# sheet1.net
KiCad netlist of a schematic drawn in Altium Designer
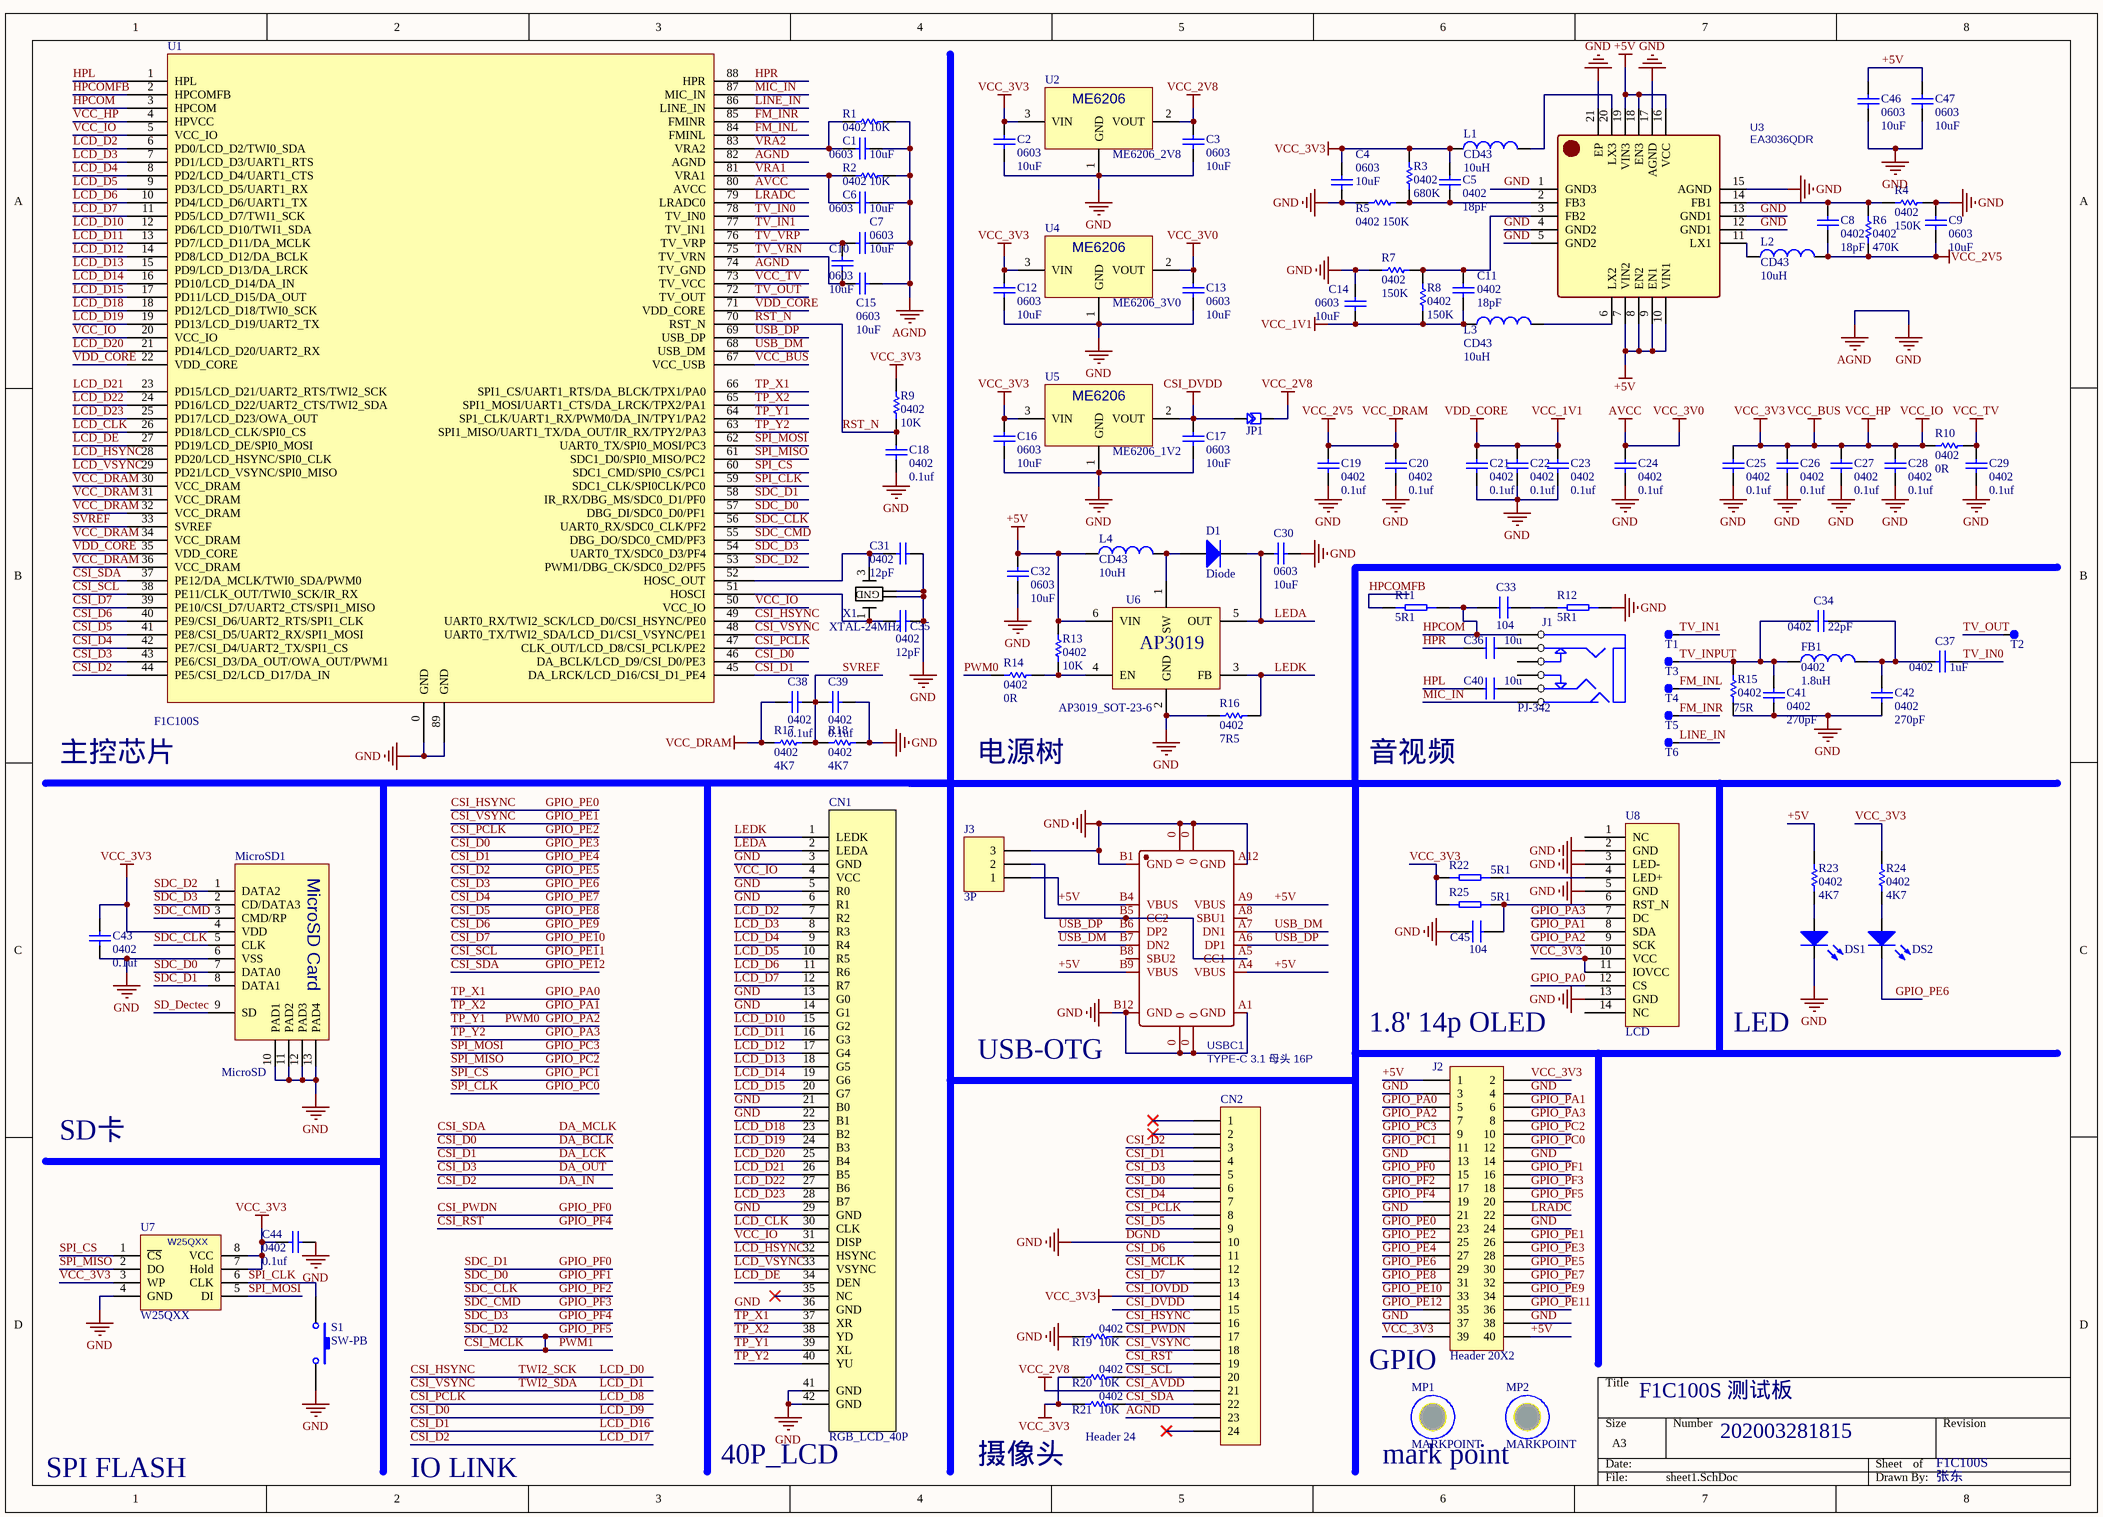
[diagram p0: sheet1.SchDoc]

(export (version "E")
  (design (tool "Eeschema 10.0.6"))
  (components
    (comp (ref "C1")
      (value "0603")
      (footprint "0603AC")
      (description "Capacitor")
      (fields (field (name "ALTIUM_VALUE") "10uF") (field (name "PUBLISHER") "Altium Limited"))
      (libsource (lib "Miscellaneous Devices") (part "Cap"))
    )
    (comp (ref "C2")
      (value "0603")
      (footprint "0603AC")
      (description "Capacitor")
      (fields (field (name "ALTIUM_VALUE") "10uF") (field (name "PUBLISHER") "Altium Limited"))
      (libsource (lib "Miscellaneous Devices") (part "Cap"))
    )
    (comp (ref "C3")
      (value "0603")
      (footprint "0603AC")
      (description "Capacitor")
      (fields (field (name "ALTIUM_VALUE") "10uF") (field (name "PUBLISHER") "Altium Limited"))
      (libsource (lib "Miscellaneous Devices") (part "Cap"))
    )
    (comp (ref "C4")
      (value "0603")
      (footprint "0603AC")
      (description "Capacitor")
      (fields (field (name "ALTIUM_VALUE") "10uF") (field (name "PUBLISHER") "Altium Limited"))
      (libsource (lib "Miscellaneous Devices") (part "Cap"))
    )
    (comp (ref "C5")
      (value "0402")
      (footprint "0402AC")
      (description "Capacitor")
      (fields (field (name "ALTIUM_VALUE") "18pF") (field (name "PUBLISHER") "Altium Limited"))
      (libsource (lib "Miscellaneous Devices") (part "Cap"))
    )
    (comp (ref "C6")
      (value "0603")
      (footprint "0603AC")
      (description "Capacitor")
      (fields (field (name "ALTIUM_VALUE") "10uF") (field (name "PUBLISHER") "Altium Limited"))
      (libsource (lib "Miscellaneous Devices") (part "Cap"))
    )
    (comp (ref "C7")
      (value "0603")
      (footprint "0603AC")
      (description "Capacitor")
      (fields (field (name "ALTIUM_VALUE") "10uF") (field (name "PUBLISHER") "Altium Limited"))
      (libsource (lib "Miscellaneous Devices") (part "Cap"))
    )
    (comp (ref "C8")
      (value "0402")
      (footprint "0402AC")
      (description "Capacitor")
      (fields (field (name "ALTIUM_VALUE") "18pF") (field (name "PUBLISHER") "Altium Limited"))
      (libsource (lib "Miscellaneous Devices") (part "Cap"))
    )
    (comp (ref "C9")
      (value "0603")
      (footprint "0603AC")
      (description "Capacitor")
      (fields (field (name "ALTIUM_VALUE") "10uF") (field (name "PUBLISHER") "Altium Limited"))
      (libsource (lib "Miscellaneous Devices") (part "Cap"))
    )
    (comp (ref "C10")
      (value "0603")
      (footprint "0603AC")
      (description "Capacitor")
      (fields (field (name "ALTIUM_VALUE") "10uF") (field (name "PUBLISHER") "Altium Limited"))
      (libsource (lib "Miscellaneous Devices") (part "Cap"))
    )
    (comp (ref "C11")
      (value "0402")
      (footprint "0402AC")
      (description "Capacitor")
      (fields (field (name "ALTIUM_VALUE") "18pF") (field (name "PUBLISHER") "Altium Limited"))
      (libsource (lib "Miscellaneous Devices") (part "Cap"))
    )
    (comp (ref "C12")
      (value "0603")
      (footprint "0603AC")
      (description "Capacitor")
      (fields (field (name "ALTIUM_VALUE") "10uF") (field (name "PUBLISHER") "Altium Limited"))
      (libsource (lib "Miscellaneous Devices") (part "Cap"))
    )
    (comp (ref "C13")
      (value "0603")
      (footprint "0603AC")
      (description "Capacitor")
      (fields (field (name "ALTIUM_VALUE") "10uF") (field (name "PUBLISHER") "Altium Limited"))
      (libsource (lib "Miscellaneous Devices") (part "Cap"))
    )
    (comp (ref "C14")
      (value "0603")
      (footprint "0603AC")
      (description "Capacitor")
      (fields (field (name "ALTIUM_VALUE") "10uF") (field (name "PUBLISHER") "Altium Limited"))
      (libsource (lib "Miscellaneous Devices") (part "Cap"))
    )
    (comp (ref "C15")
      (value "0603")
      (footprint "0603AC")
      (description "Capacitor")
      (fields (field (name "ALTIUM_VALUE") "10uF") (field (name "PUBLISHER") "Altium Limited"))
      (libsource (lib "Miscellaneous Devices") (part "Cap"))
    )
    (comp (ref "C16")
      (value "0603")
      (footprint "0603AC")
      (description "Capacitor")
      (fields (field (name "ALTIUM_VALUE") "10uF") (field (name "PUBLISHER") "Altium Limited"))
      (libsource (lib "Miscellaneous Devices") (part "Cap"))
    )
    (comp (ref "C17")
      (value "0603")
      (footprint "0603AC")
      (description "Capacitor")
      (fields (field (name "ALTIUM_VALUE") "10uF") (field (name "PUBLISHER") "Altium Limited"))
      (libsource (lib "Miscellaneous Devices") (part "Cap"))
    )
    (comp (ref "C18")
      (value "0402")
      (footprint "0402AC")
      (description "Capacitor")
      (fields (field (name "ALTIUM_VALUE") "0.1uf") (field (name "PUBLISHER") "Altium Limited"))
      (libsource (lib "Miscellaneous Devices") (part "Cap"))
    )
    (comp (ref "C19")
      (value "0402")
      (footprint "0402AC")
      (description "Capacitor")
      (fields (field (name "ALTIUM_VALUE") "0.1uf") (field (name "PUBLISHER") "Altium Limited"))
      (libsource (lib "Miscellaneous Devices") (part "Cap"))
    )
    (comp (ref "C20")
      (value "0402")
      (footprint "0402AC")
      (description "Capacitor")
      (fields (field (name "ALTIUM_VALUE") "0.1uf") (field (name "PUBLISHER") "Altium Limited"))
      (libsource (lib "Miscellaneous Devices") (part "Cap"))
    )
    (comp (ref "C21")
      (value "0402")
      (footprint "0402AC")
      (description "Capacitor")
      (fields (field (name "ALTIUM_VALUE") "0.1uf") (field (name "PUBLISHER") "Altium Limited"))
      (libsource (lib "Miscellaneous Devices") (part "Cap"))
    )
    (comp (ref "C22")
      (value "0402")
      (footprint "0402AC")
      (description "Capacitor")
      (fields (field (name "ALTIUM_VALUE") "0.1uf") (field (name "PUBLISHER") "Altium Limited"))
      (libsource (lib "Miscellaneous Devices") (part "Cap"))
    )
    (comp (ref "C23")
      (value "0402")
      (footprint "0402AC")
      (description "Capacitor")
      (fields (field (name "ALTIUM_VALUE") "0.1uf") (field (name "PUBLISHER") "Altium Limited"))
      (libsource (lib "Miscellaneous Devices") (part "Cap"))
    )
    (comp (ref "C24")
      (value "0402")
      (footprint "0402AC")
      (description "Capacitor")
      (fields (field (name "ALTIUM_VALUE") "0.1uf") (field (name "PUBLISHER") "Altium Limited"))
      (libsource (lib "Miscellaneous Devices") (part "Cap"))
    )
    (comp (ref "C25")
      (value "0402")
      (footprint "0402AC")
      (description "Capacitor")
      (fields (field (name "ALTIUM_VALUE") "0.1uf") (field (name "PUBLISHER") "Altium Limited"))
      (libsource (lib "Miscellaneous Devices") (part "Cap"))
    )
    (comp (ref "C26")
      (value "0402")
      (footprint "0402AC")
      (description "Capacitor")
      (fields (field (name "ALTIUM_VALUE") "0.1uf") (field (name "PUBLISHER") "Altium Limited"))
      (libsource (lib "Miscellaneous Devices") (part "Cap"))
    )
    (comp (ref "C27")
      (value "0402")
      (footprint "0402AC")
      (description "Capacitor")
      (fields (field (name "ALTIUM_VALUE") "0.1uf") (field (name "PUBLISHER") "Altium Limited"))
      (libsource (lib "Miscellaneous Devices") (part "Cap"))
    )
    (comp (ref "C28")
      (value "0402")
      (footprint "0402AC")
      (description "Capacitor")
      (fields (field (name "ALTIUM_VALUE") "0.1uf") (field (name "PUBLISHER") "Altium Limited"))
      (libsource (lib "Miscellaneous Devices") (part "Cap"))
    )
    (comp (ref "C29")
      (value "0402")
      (footprint "0402AC")
      (description "Capacitor")
      (fields (field (name "ALTIUM_VALUE") "0.1uf") (field (name "PUBLISHER") "Altium Limited"))
      (libsource (lib "Miscellaneous Devices") (part "Cap"))
    )
    (comp (ref "C30")
      (value "0603")
      (footprint "0603AC")
      (description "Capacitor")
      (fields (field (name "ALTIUM_VALUE") "10uF") (field (name "PUBLISHER") "Altium Limited"))
      (libsource (lib "Miscellaneous Devices") (part "Cap"))
    )
    (comp (ref "C31")
      (value "0402")
      (footprint "0402AC")
      (description "Capacitor")
      (fields (field (name "ALTIUM_VALUE") "12pF") (field (name "PUBLISHER") "Altium Limited"))
      (libsource (lib "Miscellaneous Devices") (part "Cap"))
    )
    (comp (ref "C32")
      (value "0603")
      (footprint "0603AC")
      (description "Capacitor")
      (fields (field (name "ALTIUM_VALUE") "10uF") (field (name "PUBLISHER") "Altium Limited"))
      (libsource (lib "Miscellaneous Devices") (part "Cap"))
    )
    (comp (ref "C33")
      (value "104")
      (footprint "0402C")
      (description "SMD-CAP")
      (libsource (lib "lpi-nano-dock") (part "CAP"))
    )
    (comp (ref "C34")
      (value "0402")
      (footprint "0402AC")
      (description "Capacitor")
      (fields (field (name "ALTIUM_VALUE") "22pF") (field (name "PUBLISHER") "Altium Limited"))
      (libsource (lib "Miscellaneous Devices") (part "Cap"))
    )
    (comp (ref "C35")
      (value "0402")
      (footprint "0402AC")
      (description "Capacitor")
      (fields (field (name "ALTIUM_VALUE") "12pF") (field (name "PUBLISHER") "Altium Limited"))
      (libsource (lib "Miscellaneous Devices") (part "Cap"))
    )
    (comp (ref "C36")
      (value "10u")
      (footprint "0402C")
      (description "SMD-CAP")
      (libsource (lib "lpi-nano-dock") (part "CAP"))
    )
    (comp (ref "C37")
      (value "0402")
      (footprint "0402AC")
      (description "Capacitor")
      (fields (field (name "ALTIUM_VALUE") "1uF") (field (name "PUBLISHER") "Altium Limited"))
      (libsource (lib "Miscellaneous Devices") (part "Cap"))
    )
    (comp (ref "C38")
      (value "0402")
      (footprint "0402AC")
      (description "Capacitor")
      (fields (field (name "ALTIUM_VALUE") "0.1uf") (field (name "PUBLISHER") "Altium Limited"))
      (libsource (lib "Miscellaneous Devices") (part "Cap"))
    )
    (comp (ref "C39")
      (value "0402")
      (footprint "0402AC")
      (description "Capacitor")
      (fields (field (name "ALTIUM_VALUE") "0.1uf") (field (name "PUBLISHER") "Altium Limited"))
      (libsource (lib "Miscellaneous Devices") (part "Cap"))
    )
    (comp (ref "C40")
      (value "10u")
      (footprint "0402C")
      (description "SMD-CAP")
      (libsource (lib "lpi-nano-dock") (part "CAP"))
    )
    (comp (ref "C41")
      (value "0402")
      (footprint "0402AC")
      (description "Capacitor")
      (fields (field (name "ALTIUM_VALUE") "270pF") (field (name "PUBLISHER") "Altium Limited"))
      (libsource (lib "Miscellaneous Devices") (part "Cap"))
    )
    (comp (ref "C42")
      (value "0402")
      (footprint "0402AC")
      (description "Capacitor")
      (fields (field (name "ALTIUM_VALUE") "270pF") (field (name "PUBLISHER") "Altium Limited"))
      (libsource (lib "Miscellaneous Devices") (part "Cap"))
    )
    (comp (ref "C43")
      (value "0402")
      (footprint "0402AC")
      (description "Capacitor")
      (fields (field (name "ALTIUM_VALUE") "0.1uf") (field (name "PUBLISHER") "Altium Limited"))
      (libsource (lib "Miscellaneous Devices") (part "Cap"))
    )
    (comp (ref "C44")
      (value "0402")
      (footprint "0402AC")
      (description "Capacitor")
      (fields (field (name "ALTIUM_VALUE") "0.1uf") (field (name "PUBLISHER") "Altium Limited"))
      (libsource (lib "Miscellaneous Devices") (part "Cap"))
    )
    (comp (ref "C45")
      (value "104")
      (footprint "0402C")
      (description "SMD-CAP")
      (libsource (lib "lpi-nano-dock") (part "CAP"))
    )
    (comp (ref "C46")
      (value "0603")
      (footprint "0603AC")
      (description "Capacitor")
      (fields (field (name "ALTIUM_VALUE") "10uF") (field (name "PUBLISHER") "Altium Limited"))
      (libsource (lib "Miscellaneous Devices") (part "Cap"))
    )
    (comp (ref "C47")
      (value "0603")
      (footprint "0603AC")
      (description "Capacitor")
      (fields (field (name "ALTIUM_VALUE") "10uF") (field (name "PUBLISHER") "Altium Limited"))
      (libsource (lib "Miscellaneous Devices") (part "Cap"))
    )
    (comp (ref "CN1")
      (value "RGB_LCD_40P")
      (footprint "FH19C-40S-0.5SH")
      (libsource (lib "7426SCH") (part "RGB_LCD_40P"))
    )
    (comp (ref "CN2")
      (value "Header 24")
      (footprint "FH19C-24S-0.5SH")
      (description "Header, 24-Pin")
      (fields (field (name "PUBLISHER") "Altium Limited"))
      (libsource (lib "Miscellaneous Connectors") (part "Header 24"))
    )
    (comp (ref "D1")
      (value "Diode")
      (footprint "SOD123")
      (description "Default Diode")
      (fields (field (name "PUBLISHER") "Altium Limited"))
      (libsource (lib "Miscellaneous Devices") (part "Diode"))
    )
    (comp (ref "DS1") (value "LED") (footprint "LED 0805B") (libsource (lib "QT") (part "LED")))
    (comp (ref "DS2") (value "LED") (footprint "LED 0805B") (libsource (lib "QT") (part "LED")))
    (comp (ref "FB1")
      (value "0402")
      (footprint "0402AR")
      (description "CD43")
      (fields (field (name "ALTIUM_VALUE") "1.8uH") (field (name "PUBLISHER") "Altium Limited"))
      (libsource (lib "Miscellaneous Devices") (part "Inductor"))
    )
    (comp (ref "J1") (value "PJ-342") (footprint "PJ-342") (libsource (lib "lpi-nano-dock") (part "PJ-342")))
    (comp (ref "J2")
      (value "Header 20X2")
      (footprint "HDR2X20")
      (description "Header, 20-Pin, Dual row")
      (fields (field (name "PUBLISHER") "Altium Limited"))
      (libsource (lib "Miscellaneous Connectors") (part "Header 20X2"))
    )
    (comp (ref "J3") (value "3P") (footprint "3P") (libsource (lib "常用元件库") (part "3P")))
    (comp (ref "JP1") (value "SW-PAD-2") (footprint "SW-PAD-2") (libsource (lib "7426SCH") (part "SW-PAD-2")))
    (comp (ref "L1")
      (value "CD43")
      (footprint "2520")
      (fields (field (name "ALTIUM_VALUE") "10uH") (field (name "PUBLISHER") "Altium Limited"))
      (libsource (lib "Miscellaneous Devices") (part "Inductor"))
    )
    (comp (ref "L2")
      (value "CD43")
      (footprint "2520")
      (fields (field (name "ALTIUM_VALUE") "10uH") (field (name "PUBLISHER") "Altium Limited"))
      (libsource (lib "Miscellaneous Devices") (part "Inductor"))
    )
    (comp (ref "L3")
      (value "CD43")
      (footprint "2520")
      (fields (field (name "ALTIUM_VALUE") "10uH") (field (name "PUBLISHER") "Altium Limited"))
      (libsource (lib "Miscellaneous Devices") (part "Inductor"))
    )
    (comp (ref "L4")
      (value "CD43")
      (footprint "2520")
      (fields (field (name "ALTIUM_VALUE") "10uH") (field (name "PUBLISHER") "Altium Limited"))
      (libsource (lib "Miscellaneous Devices") (part "Inductor"))
    )
    (comp (ref "MicroSD1")
      (value "MicroSD")
      (footprint "MicroSD")
      (libsource (lib "7426SCH") (part "MicroSD"))
    )
    (comp (ref "MP1")
      (value "MARKPOINT")
      (footprint "MARKPOINT")
      (libsource (lib "7426SCH") (part "MARKPOINT"))
    )
    (comp (ref "MP2")
      (value "MARKPOINT")
      (footprint "MARKPOINT")
      (libsource (lib "7426SCH") (part "MARKPOINT"))
    )
    (comp (ref "R1")
      (value "0402")
      (footprint "0402AR")
      (description "Resistor")
      (fields (field (name "ALTIUM_VALUE") "10K") (field (name "PUBLISHER") "Altium Limited"))
      (libsource (lib "Miscellaneous Devices") (part "Res1"))
    )
    (comp (ref "R2")
      (value "0402")
      (footprint "0402AR")
      (description "Resistor")
      (fields (field (name "ALTIUM_VALUE") "10K") (field (name "PUBLISHER") "Altium Limited"))
      (libsource (lib "Miscellaneous Devices") (part "Res1"))
    )
    (comp (ref "R3")
      (value "0402")
      (footprint "0402AR")
      (fields (field (name "ALTIUM_VALUE") "680K") (field (name "PUBLISHER") "Altium Limited"))
      (libsource (lib "Miscellaneous Devices") (part "Res1"))
    )
    (comp (ref "R4")
      (value "0402")
      (footprint "0402AR")
      (description "Resistor")
      (fields (field (name "ALTIUM_VALUE") "150K") (field (name "PUBLISHER") "Altium Limited"))
      (libsource (lib "Miscellaneous Devices") (part "Res1"))
    )
    (comp (ref "R5")
      (value "0402")
      (footprint "0402AR")
      (description "Resistor")
      (fields (field (name "ALTIUM_VALUE") "150K") (field (name "PUBLISHER") "Altium Limited"))
      (libsource (lib "Miscellaneous Devices") (part "Res1"))
    )
    (comp (ref "R6")
      (value "0402")
      (footprint "0402AR")
      (fields (field (name "ALTIUM_VALUE") "470K") (field (name "PUBLISHER") "Altium Limited"))
      (libsource (lib "Miscellaneous Devices") (part "Res1"))
    )
    (comp (ref "R7")
      (value "0402")
      (footprint "0402AR")
      (fields (field (name "ALTIUM_VALUE") "150K") (field (name "PUBLISHER") "Altium Limited"))
      (libsource (lib "Miscellaneous Devices") (part "Res1"))
    )
    (comp (ref "R8")
      (value "0402")
      (footprint "0402AR")
      (fields (field (name "ALTIUM_VALUE") "150K") (field (name "PUBLISHER") "Altium Limited"))
      (libsource (lib "Miscellaneous Devices") (part "Res1"))
    )
    (comp (ref "R9")
      (value "0402")
      (footprint "0402AR")
      (fields (field (name "ALTIUM_VALUE") "10K") (field (name "PUBLISHER") "Altium Limited"))
      (libsource (lib "Miscellaneous Devices") (part "Res1"))
    )
    (comp (ref "R10")
      (value "0402")
      (footprint "0402AR")
      (fields (field (name "ALTIUM_VALUE") "0R") (field (name "PUBLISHER") "Altium Limited"))
      (libsource (lib "Miscellaneous Devices") (part "Res1"))
    )
    (comp (ref "R11") (value "5R1") (footprint "0402R") (libsource (lib "lpi-nano-dock") (part "R")))
    (comp (ref "R12") (value "5R1") (footprint "0402R") (libsource (lib "lpi-nano-dock") (part "R")))
    (comp (ref "R13")
      (value "0402")
      (footprint "0402AR")
      (fields (field (name "ALTIUM_VALUE") "10K") (field (name "PUBLISHER") "Altium Limited"))
      (libsource (lib "Miscellaneous Devices") (part "Res1"))
    )
    (comp (ref "R14")
      (value "0402")
      (footprint "0402AR")
      (fields (field (name "ALTIUM_VALUE") "0R") (field (name "PUBLISHER") "Altium Limited"))
      (libsource (lib "Miscellaneous Devices") (part "Res1"))
    )
    (comp (ref "R15")
      (value "0402")
      (footprint "0402AR")
      (description "Resistor")
      (fields (field (name "ALTIUM_VALUE") "75R") (field (name "PUBLISHER") "Altium Limited"))
      (libsource (lib "Miscellaneous Devices") (part "Res1"))
    )
    (comp (ref "R16")
      (value "0402")
      (footprint "0402AR")
      (fields (field (name "ALTIUM_VALUE") "7R5") (field (name "PUBLISHER") "Altium Limited"))
      (libsource (lib "Miscellaneous Devices") (part "Res1"))
    )
    (comp (ref "R17")
      (value "0402")
      (footprint "0402AR")
      (fields (field (name "ALTIUM_VALUE") "4K7") (field (name "PUBLISHER") "Altium Limited"))
      (libsource (lib "Miscellaneous Devices") (part "Res1"))
    )
    (comp (ref "R18")
      (value "0402")
      (footprint "0402AR")
      (fields (field (name "ALTIUM_VALUE") "4K7") (field (name "PUBLISHER") "Altium Limited"))
      (libsource (lib "Miscellaneous Devices") (part "Res1"))
    )
    (comp (ref "R19")
      (value "0402")
      (footprint "0402AR")
      (fields (field (name "ALTIUM_VALUE") "10K") (field (name "PUBLISHER") "Altium Limited"))
      (libsource (lib "Miscellaneous Devices") (part "Res1"))
    )
    (comp (ref "R20")
      (value "0402")
      (footprint "0402AR")
      (fields (field (name "ALTIUM_VALUE") "10K") (field (name "PUBLISHER") "Altium Limited"))
      (libsource (lib "Miscellaneous Devices") (part "Res1"))
    )
    (comp (ref "R21")
      (value "0402")
      (footprint "0402AR")
      (fields (field (name "ALTIUM_VALUE") "10K") (field (name "PUBLISHER") "Altium Limited"))
      (libsource (lib "Miscellaneous Devices") (part "Res1"))
    )
    (comp (ref "R22") (value "5R1") (footprint "0402R") (libsource (lib "lpi-nano-dock") (part "R")))
    (comp (ref "R23")
      (value "0402")
      (footprint "0402AR")
      (fields (field (name "ALTIUM_VALUE") "4K7") (field (name "PUBLISHER") "Altium Limited"))
      (libsource (lib "PineapplePi-F1") (part "Res1"))
    )
    (comp (ref "R24")
      (value "0402")
      (footprint "0402AR")
      (fields (field (name "ALTIUM_VALUE") "4K7") (field (name "PUBLISHER") "Altium Limited"))
      (libsource (lib "PineapplePi-F1") (part "Res1"))
    )
    (comp (ref "R25") (value "5R1") (footprint "0402R") (libsource (lib "lpi-nano-dock") (part "R")))
    (comp (ref "S1")
      (value "SW-PB")
      (footprint "SW-SMD1")
      (description "Switch")
      (fields (field (name "PUBLISHER") "Altium Limited"))
      (libsource (lib "Miscellaneous Devices") (part "SW-PB"))
    )
    (comp (ref "T1") (value "1 测试点") (footprint "SIP1-1*1") (libsource (lib "常用元件库") (part "1 测试点")))
    (comp (ref "T2") (value "1 测试点") (footprint "SIP1-1*1") (libsource (lib "常用元件库") (part "1 测试点")))
    (comp (ref "T3") (value "1 测试点") (footprint "SIP1-1*1") (libsource (lib "常用元件库") (part "1 测试点")))
    (comp (ref "T4") (value "1 测试点") (footprint "SIP1-1*1") (libsource (lib "常用元件库") (part "1 测试点")))
    (comp (ref "T5") (value "1 测试点") (footprint "SIP1-1*1") (libsource (lib "常用元件库") (part "1 测试点")))
    (comp (ref "T6") (value "1 测试点") (footprint "SIP1-1*1") (libsource (lib "常用元件库") (part "1 测试点")))
    (comp (ref "U1") (value "F1C100S") (footprint "QFN88-10X10") (libsource (lib "7426SCH") (part "F1C100S")))
    (comp (ref "U2") (value "ME6206_2V8") (footprint "SOT-23") (libsource (lib "IC") (part "ME6206")))
    (comp (ref "U3")
      (value "EA3036QDR")
      (footprint "QFN20-3x3-0.4")
      (fields (field (name "BOM_SUPPLIER PART") "C111587"))
      (libsource (lib "IC") (part "EA3036QDR"))
    )
    (comp (ref "U4") (value "ME6206_3V0") (footprint "SOT-23") (libsource (lib "IC") (part "ME6206")))
    (comp (ref "U5") (value "ME6206_1V2") (footprint "SOT-23") (libsource (lib "IC") (part "ME6206")))
    (comp (ref "U6") (value "AP3019_SOT-23-6") (footprint "SOT23-6") (libsource (lib "IC") (part "AP3019")))
    (comp (ref "U7") (value "W25QXX") (footprint "SO-8M") (libsource (lib "IC") (part "W25QXX")))
    (comp (ref "U8")
      (value "LCD")
      (footprint "LCD_SPI_14P_sim")
      (libsource (lib "lpi-nano-dock") (part "LCD_SPI_14P"))
    )
    (comp (ref "USBC1")
      (value "TYPE-C 3.1 母头 16P")
      (footprint "TYPE-C-USB-12")
      (libsource (lib "Interface") (part "TYPE-C 3.1 母头 16P"))
    )
    (comp (ref "X1")
      (value "XTAL-24MHz")
      (footprint "XTAL-3225")
      (libsource (lib "7426SCH") (part "XTAL-SMD"))
    )
  )
  (nets
    (net (code "1") (name "+5V") (class "Default")
      (node (ref "C32") (pin "2") (pinfunction "2_2") (pintype "passive"))
      (node (ref "C46") (pin "2") (pinfunction "2_2") (pintype "passive"))
      (node (ref "C47") (pin "2") (pinfunction "2_2") (pintype "passive"))
      (node (ref "J2") (pin "1") (pinfunction "1_1") (pintype "passive"))
      (node (ref "J2") (pin "40") (pinfunction "40_40") (pintype "passive"))
      (node (ref "J3") (pin "1") (pinfunction "1_1") (pintype "passive"))
      (node (ref "L4") (pin "1") (pinfunction "1_1") (pintype "passive"))
      (node (ref "R13") (pin "1") (pinfunction "1_1") (pintype "passive"))
      (node (ref "R23") (pin "2") (pinfunction "2_2") (pintype "passive"))
      (node (ref "U3") (pin "10") (pinfunction "VIN1_10") (pintype "passive"))
      (node (ref "U3") (pin "16") (pinfunction "VCC_16") (pintype "passive"))
      (node (ref "U3") (pin "18") (pinfunction "EN3_18") (pintype "passive"))
      (node (ref "U3") (pin "19") (pinfunction "VIN3_19") (pintype "passive"))
      (node (ref "U3") (pin "7") (pinfunction "VIN2_7") (pintype "passive"))
      (node (ref "U3") (pin "8") (pinfunction "EN2_8") (pintype "passive"))
      (node (ref "U3") (pin "9") (pinfunction "EN1_9") (pintype "passive"))
      (node (ref "U6") (pin "6") (pinfunction "VIN_6") (pintype "passive"))
      (node (ref "USBC1") (pin "A4") (pinfunction "VBUS_A4") (pintype "passive"))
      (node (ref "USBC1") (pin "A9") (pinfunction "VBUS_A9") (pintype "passive"))
      (node (ref "USBC1") (pin "B4") (pinfunction "VBUS_B4") (pintype "passive"))
      (node (ref "USBC1") (pin "B9") (pinfunction "VBUS_B9") (pintype "passive"))
    )
    (net (code "2") (name "/CSI_D0") (class "Default")
      (node (ref "CN2") (pin "6") (pinfunction "6_6") (pintype "passive"))
      (node (ref "J2") (pin "28") (pinfunction "28_28") (pintype "passive"))
      (node (ref "U1") (pin "46") (pinfunction "DA_BCLK/LCD_D9/CSI_D0/PE3_46") (pintype "passive"))
    )
    (net (code "3") (name "/CSI_D1") (class "Default")
      (node (ref "CN2") (pin "4") (pinfunction "4_4") (pintype "passive"))
      (node (ref "J2") (pin "27") (pinfunction "27_27") (pintype "passive"))
      (node (ref "U1") (pin "45") (pinfunction "DA_LRCK/LCD_D16/CSI_D1_PE4_45") (pintype "passive"))
    )
    (net (code "4") (name "/CSI_D2") (class "Default")
      (node (ref "CN2") (pin "3") (pinfunction "3_3") (pintype "passive"))
      (node (ref "J2") (pin "30") (pinfunction "30_30") (pintype "passive"))
      (node (ref "U1") (pin "44") (pinfunction "PE5/CSI_D2/LCD_D17/DA_IN_44") (pintype "passive"))
    )
    (net (code "5") (name "/CSI_D3") (class "Default")
      (node (ref "CN2") (pin "5") (pinfunction "5_5") (pintype "passive"))
      (node (ref "DS2") (pin "2") (pinfunction "K_2") (pintype "passive"))
      (node (ref "J2") (pin "29") (pinfunction "29_29") (pintype "passive"))
      (node (ref "U1") (pin "43") (pinfunction "PE6/CSI_D3/DA_OUT/OWA_OUT/PWM1_43") (pintype "passive"))
    )
    (net (code "6") (name "/CSI_D4") (class "Default")
      (node (ref "CN2") (pin "7") (pinfunction "7_7") (pintype "passive"))
      (node (ref "J2") (pin "32") (pinfunction "32_32") (pintype "passive"))
      (node (ref "U1") (pin "42") (pinfunction "PE7/CSI_D4/UART2_TX/SPI1_CS_42") (pintype "passive"))
    )
    (net (code "7") (name "/CSI_D5") (class "Default")
      (node (ref "CN2") (pin "9") (pinfunction "9_9") (pintype "passive"))
      (node (ref "J2") (pin "31") (pinfunction "31_31") (pintype "passive"))
      (node (ref "U1") (pin "41") (pinfunction "PE8/CSI_D5/UART2_RX/SPI1_MOSI_41") (pintype "passive"))
    )
    (net (code "8") (name "/CSI_D6") (class "Default")
      (node (ref "CN2") (pin "11") (pinfunction "11_11") (pintype "passive"))
      (node (ref "J2") (pin "34") (pinfunction "34_34") (pintype "passive"))
      (node (ref "U1") (pin "40") (pinfunction "PE9/CSI_D6/UART2_RTS/SPI1_CLK_40") (pintype "passive"))
    )
    (net (code "9") (name "/CSI_D7") (class "Default")
      (node (ref "CN2") (pin "13") (pinfunction "13_13") (pintype "passive"))
      (node (ref "J2") (pin "33") (pinfunction "33_33") (pintype "passive"))
      (node (ref "U1") (pin "39") (pinfunction "PE10/CSI_D7/UART2_CTS/SPI1_MISO_39") (pintype "passive"))
    )
    (net (code "10") (name "/CSI_HSYNC") (class "Default")
      (node (ref "CN2") (pin "16") (pinfunction "16_16") (pintype "passive"))
      (node (ref "J2") (pin "23") (pinfunction "23_23") (pintype "passive"))
      (node (ref "U1") (pin "49") (pinfunction "UART0_RX/TWI2_SCK/LCD_D0/CSI_HSYNC/PE0_49") (pintype "passive"))
    )
    (net (code "11") (name "/CSI_MCLK") (class "Default")
      (node (ref "CN2") (pin "12") (pinfunction "12_12") (pintype "passive"))
      (node (ref "J2") (pin "20") (pinfunction "20_20") (pintype "passive"))
      (node (ref "MicroSD1") (pin "1") (pinfunction "DATA2_1") (pintype "power_in"))
      (node (ref "U1") (pin "53") (pinfunction "PWM1/DBG_CK/SDC0_D2/PF5_53") (pintype "passive"))
    )
    (net (code "12") (name "/CSI_PCLK") (class "Default")
      (node (ref "CN2") (pin "8") (pinfunction "8_8") (pintype "passive"))
      (node (ref "J2") (pin "25") (pinfunction "25_25") (pintype "passive"))
      (node (ref "U1") (pin "47") (pinfunction "CLK_OUT/LCD_D8/CSI_PCLK/PE2_47") (pintype "passive"))
    )
    (net (code "13") (name "/CSI_PWDN") (class "Default")
      (node (ref "CN2") (pin "17") (pinfunction "17_17") (pintype "passive"))
      (node (ref "J2") (pin "15") (pinfunction "15_15") (pintype "passive"))
      (node (ref "MicroSD1") (pin "8") (pinfunction "DATA1_8") (pintype "power_in"))
      (node (ref "R19") (pin "2") (pinfunction "2_2") (pintype "passive"))
      (node (ref "U1") (pin "58") (pinfunction "IR_RX/DBG_MS/SDC0_D1/PF0_58") (pintype "passive"))
    )
    (net (code "14") (name "/CSI_RST") (class "Default")
      (node (ref "CN2") (pin "19") (pinfunction "19_19") (pintype "passive"))
      (node (ref "J2") (pin "19") (pinfunction "19_19") (pintype "passive"))
      (node (ref "MicroSD1") (pin "2") (pinfunction "CD/DATA3_2") (pintype "power_in"))
      (node (ref "U1") (pin "54") (pinfunction "UART0_TX/SDC0_D3/PF4_54") (pintype "passive"))
    )
    (net (code "15") (name "/CSI_SCL") (class "Default")
      (node (ref "CN2") (pin "20") (pinfunction "20_20") (pintype "passive"))
      (node (ref "J2") (pin "36") (pinfunction "36_36") (pintype "passive"))
      (node (ref "R20") (pin "1") (pinfunction "1_1") (pintype "passive"))
      (node (ref "U1") (pin "38") (pinfunction "PE11/CLK_OUT/TWI0_SCK/IR_RX_38") (pintype "passive"))
    )
    (net (code "16") (name "/CSI_SDA") (class "Default")
      (node (ref "CN2") (pin "22") (pinfunction "22_22") (pintype "passive"))
      (node (ref "J2") (pin "35") (pinfunction "35_35") (pintype "passive"))
      (node (ref "R21") (pin "1") (pinfunction "1_1") (pintype "passive"))
      (node (ref "U1") (pin "37") (pinfunction "PE12/DA_MCLK/TWI0_SDA/PWM0_37") (pintype "passive"))
    )
    (net (code "17") (name "/CSI_VSYNC") (class "Default")
      (node (ref "CN2") (pin "18") (pinfunction "18_18") (pintype "passive"))
      (node (ref "J2") (pin "26") (pinfunction "26_26") (pintype "passive"))
      (node (ref "U1") (pin "48") (pinfunction "UART0_TX/TWI2_SDA/LCD_D1/CSI_VSYNC/PE1_48") (pintype "passive"))
    )
    (net (code "18") (name "/FM_INL") (class "Default")
      (node (ref "T4") (pin "1") (pintype "passive"))
      (node (ref "U1") (pin "84") (pinfunction "FMINL_84") (pintype "passive"))
    )
    (net (code "19") (name "/FM_INR") (class "Default")
      (node (ref "T5") (pin "1") (pintype "passive"))
      (node (ref "U1") (pin "85") (pinfunction "FMINR_85") (pintype "passive"))
    )
    (net (code "20") (name "/GPIO_PA0") (class "Default")
      (node (ref "CN1") (pin "37") (pinfunction "XR_37") (pintype "passive"))
      (node (ref "J2") (pin "5") (pinfunction "5_5") (pintype "passive"))
      (node (ref "U1") (pin "66") (pinfunction "SPI1_CS/UART1_RTS/DA_BLCK/TPX1/PA0_66") (pintype "passive"))
      (node (ref "U8") (pin "12") (pinfunction "CS_12") (pintype "passive"))
    )
    (net (code "21") (name "/GPIO_PA1") (class "Default")
      (node (ref "CN1") (pin "38") (pinfunction "YD_38") (pintype "passive"))
      (node (ref "J2") (pin "6") (pinfunction "6_6") (pintype "passive"))
      (node (ref "U1") (pin "65") (pinfunction "SPI1_MOSI/UART1_CTS/DA_LRCK/TPX2/PA1_65") (pintype "passive"))
      (node (ref "U8") (pin "8") (pinfunction "SDA_8") (pintype "passive"))
    )
    (net (code "22") (name "/GPIO_PA2") (class "Default")
      (node (ref "CN1") (pin "39") (pinfunction "XL_39") (pintype "passive"))
      (node (ref "J2") (pin "7") (pinfunction "7_7") (pintype "passive"))
      (node (ref "R14") (pin "1") (pinfunction "1_1") (pintype "passive"))
      (node (ref "U1") (pin "64") (pinfunction "SP1_CLK/UART1_RX/PWM0/DA_IN/TPY1/PA2_64") (pintype "passive"))
      (node (ref "U8") (pin "9") (pinfunction "SCK_9") (pintype "passive"))
    )
    (net (code "23") (name "/GPIO_PA3") (class "Default")
      (node (ref "CN1") (pin "40") (pinfunction "YU_40") (pintype "passive"))
      (node (ref "J2") (pin "8") (pinfunction "8_8") (pintype "passive"))
      (node (ref "U1") (pin "63") (pinfunction "SPI1_MISO/UART1_TX/DA_OUT/IR_RX/TPY2/PA3_63") (pintype "passive"))
      (node (ref "U8") (pin "7") (pinfunction "DC_7") (pintype "passive"))
    )
    (net (code "24") (name "/GPIO_PC0") (class "Default")
      (node (ref "J2") (pin "12") (pinfunction "12_12") (pintype "passive"))
      (node (ref "S1") (pin "1") (pinfunction "1_1") (pintype "passive"))
      (node (ref "U1") (pin "59") (pinfunction "SDC1_CLK/SPI0CLK/PC0_59") (pintype "passive"))
      (node (ref "U7") (pin "6") (pinfunction "CLK_6") (pintype "power_in"))
    )
    (net (code "25") (name "/GPIO_PC1") (class "Default")
      (node (ref "J2") (pin "11") (pinfunction "11_11") (pintype "passive"))
      (node (ref "U1") (pin "60") (pinfunction "SDC1_CMD/SPI0_CS/PC1_60") (pintype "passive"))
      (node (ref "U7") (pin "1") (pinfunction "~{CS}_1") (pintype "power_in"))
    )
    (net (code "26") (name "/GPIO_PC2") (class "Default")
      (node (ref "J2") (pin "10") (pinfunction "10_10") (pintype "passive"))
      (node (ref "U1") (pin "61") (pinfunction "SDC1_D0/SPI0_MISO/PC2_61") (pintype "passive"))
      (node (ref "U7") (pin "2") (pinfunction "DO_2") (pintype "power_in"))
    )
    (net (code "27") (name "/GPIO_PC3") (class "Default")
      (node (ref "J2") (pin "9") (pinfunction "9_9") (pintype "passive"))
      (node (ref "U1") (pin "62") (pinfunction "UART0_TX/SPI0_MOSI/PC3_62") (pintype "passive"))
      (node (ref "U7") (pin "5") (pinfunction "DI_5") (pintype "power_in"))
    )
    (net (code "28") (name "/GPIO_PF1") (class "Default")
      (node (ref "J2") (pin "16") (pinfunction "16_16") (pintype "passive"))
      (node (ref "MicroSD1") (pin "7") (pinfunction "DATA0_7") (pintype "power_in"))
      (node (ref "U1") (pin "57") (pinfunction "DBG_DI/SDC0_D0/PF1_57") (pintype "passive"))
    )
    (net (code "29") (name "/GPIO_PF2") (class "Default")
      (node (ref "J2") (pin "17") (pinfunction "17_17") (pintype "passive"))
      (node (ref "MicroSD1") (pin "5") (pinfunction "CLK_5") (pintype "power_in"))
      (node (ref "U1") (pin "56") (pinfunction "UART0_RX/SDC0_CLK/PF2_56") (pintype "passive"))
    )
    (net (code "30") (name "/GPIO_PF3") (class "Default")
      (node (ref "J2") (pin "18") (pinfunction "18_18") (pintype "passive"))
      (node (ref "MicroSD1") (pin "3") (pinfunction "CMD/RP_3") (pintype "power_in"))
      (node (ref "U1") (pin "55") (pinfunction "DBG_DO/SDC0_CMD/PF3_55") (pintype "passive"))
    )
    (net (code "31") (name "/HPCOM") (class "Default")
      (node (ref "C33") (pin "1") (pinfunction "1_1") (pintype "passive"))
      (node (ref "J1") (pin "2") (pinfunction "MIC_2") (pintype "passive"))
      (node (ref "R11") (pin "2") (pinfunction "2_2") (pintype "passive"))
      (node (ref "U1") (pin "3") (pinfunction "HPCOM_3") (pintype "passive"))
    )
    (net (code "32") (name "/HPCOMFB") (class "Default")
      (node (ref "R11") (pin "1") (pinfunction "1_1") (pintype "passive"))
      (node (ref "U1") (pin "2") (pinfunction "HPCOMFB_2") (pintype "passive"))
    )
    (net (code "33") (name "/HPL") (class "Default")
      (node (ref "C40") (pin "2") (pinfunction "2_2") (pintype "passive"))
      (node (ref "U1") (pin "1") (pinfunction "HPL_1") (pintype "passive"))
    )
    (net (code "34") (name "/HPR") (class "Default")
      (node (ref "C36") (pin "1") (pinfunction "1_1") (pintype "passive"))
      (node (ref "U1") (pin "88") (pinfunction "HPR_88") (pintype "passive"))
    )
    (net (code "35") (name "/LCD_CLK") (class "Default")
      (node (ref "CN1") (pin "30") (pinfunction "CLK_30") (pintype "passive"))
      (node (ref "U1") (pin "26") (pinfunction "PD18/LCD_CLK/SPI0_CS_26") (pintype "passive"))
    )
    (net (code "36") (name "/LCD_D2") (class "Default")
      (node (ref "CN1") (pin "7") (pinfunction "R2_7") (pintype "passive"))
      (node (ref "U1") (pin "6") (pinfunction "PD0/LCD_D2/TWI0_SDA_6") (pintype "passive"))
    )
    (net (code "37") (name "/LCD_D3") (class "Default")
      (node (ref "CN1") (pin "8") (pinfunction "R3_8") (pintype "passive"))
      (node (ref "U1") (pin "7") (pinfunction "PD1/LCD_D3/UART1_RTS_7") (pintype "passive"))
    )
    (net (code "38") (name "/LCD_D4") (class "Default")
      (node (ref "CN1") (pin "9") (pinfunction "R4_9") (pintype "passive"))
      (node (ref "U1") (pin "8") (pinfunction "PD2/LCD_D4/UART1_CTS_8") (pintype "passive"))
    )
    (net (code "39") (name "/LCD_D5") (class "Default")
      (node (ref "CN1") (pin "10") (pinfunction "R5_10") (pintype "passive"))
      (node (ref "U1") (pin "9") (pinfunction "PD3/LCD_D5/UART1_RX_9") (pintype "passive"))
    )
    (net (code "40") (name "/LCD_D6") (class "Default")
      (node (ref "CN1") (pin "11") (pinfunction "R6_11") (pintype "passive"))
      (node (ref "U1") (pin "10") (pinfunction "PD4/LCD_D6/UART1_TX_10") (pintype "passive"))
    )
    (net (code "41") (name "/LCD_D7") (class "Default")
      (node (ref "CN1") (pin "12") (pinfunction "R7_12") (pintype "passive"))
      (node (ref "U1") (pin "11") (pinfunction "PD5/LCD_D7/TWI1_SCK_11") (pintype "passive"))
    )
    (net (code "42") (name "/LCD_D10") (class "Default")
      (node (ref "CN1") (pin "15") (pinfunction "G2_15") (pintype "passive"))
      (node (ref "U1") (pin "12") (pinfunction "PD6/LCD_D10/TWI1_SDA_12") (pintype "passive"))
    )
    (net (code "43") (name "/LCD_D11") (class "Default")
      (node (ref "CN1") (pin "16") (pinfunction "G3_16") (pintype "passive"))
      (node (ref "U1") (pin "13") (pinfunction "PD7/LCD_D11/DA_MCLK_13") (pintype "passive"))
    )
    (net (code "44") (name "/LCD_D12") (class "Default")
      (node (ref "CN1") (pin "17") (pinfunction "G4_17") (pintype "passive"))
      (node (ref "U1") (pin "14") (pinfunction "PD8/LCD_D12/DA_BCLK_14") (pintype "passive"))
    )
    (net (code "45") (name "/LCD_D13") (class "Default")
      (node (ref "CN1") (pin "18") (pinfunction "G5_18") (pintype "passive"))
      (node (ref "U1") (pin "15") (pinfunction "PD9/LCD_D13/DA_LRCK_15") (pintype "passive"))
    )
    (net (code "46") (name "/LCD_D14") (class "Default")
      (node (ref "CN1") (pin "19") (pinfunction "G6_19") (pintype "passive"))
      (node (ref "U1") (pin "16") (pinfunction "PD10/LCD_D14/DA_IN_16") (pintype "passive"))
    )
    (net (code "47") (name "/LCD_D15") (class "Default")
      (node (ref "CN1") (pin "20") (pinfunction "G7_20") (pintype "passive"))
      (node (ref "U1") (pin "17") (pinfunction "PD11/LCD_D15/DA_OUT_17") (pintype "passive"))
    )
    (net (code "48") (name "/LCD_D18") (class "Default")
      (node (ref "CN1") (pin "23") (pinfunction "B2_23") (pintype "passive"))
      (node (ref "U1") (pin "18") (pinfunction "PD12/LCD_D18/TWI0_SCK_18") (pintype "passive"))
    )
    (net (code "49") (name "/LCD_D19") (class "Default")
      (node (ref "CN1") (pin "24") (pinfunction "B3_24") (pintype "passive"))
      (node (ref "U1") (pin "19") (pinfunction "PD13/LCD_D19/UART2_TX_19") (pintype "passive"))
    )
    (net (code "50") (name "/LCD_D20") (class "Default")
      (node (ref "CN1") (pin "25") (pinfunction "B4_25") (pintype "passive"))
      (node (ref "U1") (pin "21") (pinfunction "PD14/LCD_D20/UART2_RX_21") (pintype "passive"))
    )
    (net (code "51") (name "/LCD_D21") (class "Default")
      (node (ref "CN1") (pin "26") (pinfunction "B5_26") (pintype "passive"))
      (node (ref "U1") (pin "23") (pinfunction "PD15/LCD_D21/UART2_RTS/TWI2_SCK_23") (pintype "passive"))
    )
    (net (code "52") (name "/LCD_D22") (class "Default")
      (node (ref "CN1") (pin "27") (pinfunction "B6_27") (pintype "passive"))
      (node (ref "U1") (pin "24") (pinfunction "PD16/LCD_D22/UART2_CTS/TWI2_SDA_24") (pintype "passive"))
    )
    (net (code "53") (name "/LCD_D23") (class "Default")
      (node (ref "CN1") (pin "28") (pinfunction "B7_28") (pintype "passive"))
      (node (ref "U1") (pin "25") (pinfunction "PD17/LCD_D23/OWA_OUT_25") (pintype "passive"))
    )
    (net (code "54") (name "/LCD_DE") (class "Default")
      (node (ref "CN1") (pin "34") (pinfunction "DEN_34") (pintype "passive"))
      (node (ref "U1") (pin "27") (pinfunction "PD19/LCD_DE/SPI0_MOSI_27") (pintype "passive"))
    )
    (net (code "55") (name "/LCD_HSYNC") (class "Default")
      (node (ref "CN1") (pin "32") (pinfunction "HSYNC_32") (pintype "passive"))
      (node (ref "U1") (pin "28") (pinfunction "PD20/LCD_HSYNC/SPI0_CLK_28") (pintype "passive"))
    )
    (net (code "56") (name "/LCD_VSYNC") (class "Default")
      (node (ref "CN1") (pin "33") (pinfunction "VSYNC_33") (pintype "passive"))
      (node (ref "U1") (pin "29") (pinfunction "PD21/LCD_VSYNC/SPI0_MISO_29") (pintype "passive"))
    )
    (net (code "57") (name "/LEDA") (class "Default")
      (node (ref "C30") (pin "1") (pinfunction "1_1") (pintype "passive"))
      (node (ref "CN1") (pin "2") (pinfunction "LEDA_2") (pintype "passive"))
      (node (ref "D1") (pin "2") (pinfunction "K_2") (pintype "passive"))
      (node (ref "U6") (pin "5") (pinfunction "OUT_5") (pintype "passive"))
    )
    (net (code "58") (name "/LEDK") (class "Default")
      (node (ref "CN1") (pin "1") (pinfunction "LEDK_1") (pintype "passive"))
      (node (ref "R16") (pin "2") (pinfunction "2_2") (pintype "passive"))
      (node (ref "U6") (pin "3") (pinfunction "FB_3") (pintype "passive"))
    )
    (net (code "59") (name "/LINE_IN") (class "Default")
      (node (ref "T6") (pin "1") (pintype "passive"))
      (node (ref "U1") (pin "86") (pinfunction "LINE_IN_86") (pintype "passive"))
    )
    (net (code "60") (name "/LRADC") (class "Default")
      (node (ref "J2") (pin "22") (pinfunction "22_22") (pintype "passive"))
      (node (ref "U1") (pin "79") (pinfunction "LRADC0_79") (pintype "passive"))
    )
    (net (code "61") (name "/MIC_IN") (class "Default")
      (node (ref "J1") (pin "3") (pinfunction "GND_3") (pintype "passive"))
      (node (ref "U1") (pin "87") (pinfunction "MIC_IN_87") (pintype "passive"))
    )
    (net (code "62") (name "/RST_N") (class "Default")
      (node (ref "C18") (pin "2") (pinfunction "2_2") (pintype "passive"))
      (node (ref "R9") (pin "1") (pinfunction "1_1") (pintype "passive"))
      (node (ref "U1") (pin "70") (pinfunction "RST_N_70") (pintype "passive"))
    )
    (net (code "63") (name "/SD_Dectec") (class "Default")
      (node (ref "MicroSD1") (pin "9") (pinfunction "SD_9") (pintype "power_in"))
    )
    (net (code "64") (name "/SVREF") (class "Default")
      (node (ref "C38") (pin "1") (pinfunction "1_1") (pintype "passive"))
      (node (ref "C39") (pin "2") (pinfunction "2_2") (pintype "passive"))
      (node (ref "R17") (pin "1") (pinfunction "1_1") (pintype "passive"))
      (node (ref "R18") (pin "2") (pinfunction "2_2") (pintype "passive"))
      (node (ref "U1") (pin "33") (pinfunction "SVREF_33") (pintype "passive"))
    )
    (net (code "65") (name "/TV_IN0") (class "Default")
      (node (ref "C37") (pin "1") (pinfunction "1_1") (pintype "passive"))
      (node (ref "U1") (pin "78") (pinfunction "TV_IN0_78") (pintype "passive"))
    )
    (net (code "66") (name "/TV_IN1") (class "Default")
      (node (ref "T1") (pin "1") (pintype "passive"))
      (node (ref "U1") (pin "77") (pinfunction "TV_IN1_77") (pintype "passive"))
    )
    (net (code "67") (name "/TV_INPUT") (class "Default")
      (node (ref "C34") (pin "2") (pinfunction "2_2") (pintype "passive"))
      (node (ref "C41") (pin "1") (pinfunction "1_1") (pintype "passive"))
      (node (ref "FB1") (pin "1") (pinfunction "1_1") (pintype "passive"))
      (node (ref "R15") (pin "2") (pinfunction "2_2") (pintype "passive"))
      (node (ref "T3") (pin "1") (pintype "passive"))
    )
    (net (code "68") (name "/TV_OUT") (class "Default")
      (node (ref "T2") (pin "1") (pintype "passive"))
      (node (ref "U1") (pin "72") (pinfunction "TV_OUT_72") (pintype "passive"))
    )
    (net (code "69") (name "/TV_VRN") (class "Default")
      (node (ref "C10") (pin "1") (pinfunction "1_1") (pintype "passive"))
      (node (ref "C15") (pin "1") (pinfunction "1_1") (pintype "passive"))
      (node (ref "U1") (pin "75") (pinfunction "TV_VRN_75") (pintype "passive"))
    )
    (net (code "70") (name "/TV_VRP") (class "Default")
      (node (ref "C10") (pin "2") (pinfunction "2_2") (pintype "passive"))
      (node (ref "C7") (pin "1") (pinfunction "1_1") (pintype "passive"))
      (node (ref "U1") (pin "76") (pinfunction "TV_VRP_76") (pintype "passive"))
    )
    (net (code "71") (name "/USB_DM") (class "Default")
      (node (ref "U1") (pin "68") (pinfunction "USB_DM_68") (pintype "passive"))
      (node (ref "USBC1") (pin "A7") (pinfunction "DN1_A7") (pintype "passive"))
      (node (ref "USBC1") (pin "B7") (pinfunction "DN2_B7") (pintype "passive"))
    )
    (net (code "72") (name "/USB_DP") (class "Default")
      (node (ref "U1") (pin "69") (pinfunction "USB_DP_69") (pintype "passive"))
      (node (ref "USBC1") (pin "A6") (pinfunction "DP1_A6") (pintype "passive"))
      (node (ref "USBC1") (pin "B6") (pinfunction "DP2_B6") (pintype "passive"))
    )
    (net (code "73") (name "/VRA1") (class "Default")
      (node (ref "C6") (pin "1") (pinfunction "1_1") (pintype "passive"))
      (node (ref "R2") (pin "2") (pinfunction "2_2") (pintype "passive"))
      (node (ref "U1") (pin "81") (pinfunction "VRA1_81") (pintype "passive"))
    )
    (net (code "74") (name "/VRA2") (class "Default")
      (node (ref "C1") (pin "1") (pinfunction "1_1") (pintype "passive"))
      (node (ref "R1") (pin "2") (pinfunction "2_2") (pintype "passive"))
      (node (ref "U1") (pin "83") (pinfunction "VRA2_83") (pintype "passive"))
    )
    (net (code "75") (name "AGND") (class "Default")
      (node (ref "C1") (pin "2") (pinfunction "2_2") (pintype "passive"))
      (node (ref "C12") (pin "1") (pinfunction "1_1") (pintype "passive"))
      (node (ref "C13") (pin "1") (pinfunction "1_1") (pintype "passive"))
      (node (ref "C14") (pin "1") (pinfunction "1_1") (pintype "passive"))
      (node (ref "C15") (pin "2") (pinfunction "2_2") (pintype "passive"))
      (node (ref "C16") (pin "1") (pinfunction "1_1") (pintype "passive"))
      (node (ref "C17") (pin "1") (pinfunction "1_1") (pintype "passive"))
      (node (ref "C18") (pin "1") (pinfunction "1_1") (pintype "passive"))
      (node (ref "C19") (pin "1") (pinfunction "1_1") (pintype "passive"))
      (node (ref "C2") (pin "1") (pinfunction "1_1") (pintype "passive"))
      (node (ref "C20") (pin "1") (pinfunction "1_1") (pintype "passive"))
      (node (ref "C21") (pin "1") (pinfunction "1_1") (pintype "passive"))
      (node (ref "C22") (pin "1") (pinfunction "1_1") (pintype "passive"))
      (node (ref "C23") (pin "1") (pinfunction "1_1") (pintype "passive"))
      (node (ref "C24") (pin "1") (pinfunction "1_1") (pintype "passive"))
      (node (ref "C25") (pin "2") (pinfunction "2_2") (pintype "passive"))
      (node (ref "C26") (pin "1") (pinfunction "1_1") (pintype "passive"))
      (node (ref "C27") (pin "1") (pinfunction "1_1") (pintype "passive"))
      (node (ref "C28") (pin "1") (pinfunction "1_1") (pintype "passive"))
      (node (ref "C29") (pin "1") (pinfunction "1_1") (pintype "passive"))
      (node (ref "C3") (pin "1") (pinfunction "1_1") (pintype "passive"))
      (node (ref "C30") (pin "2") (pinfunction "2_2") (pintype "passive"))
      (node (ref "C31") (pin "1") (pinfunction "1_1") (pintype "passive"))
      (node (ref "C32") (pin "1") (pinfunction "1_1") (pintype "passive"))
      (node (ref "C35") (pin "1") (pinfunction "1_1") (pintype "passive"))
      (node (ref "C39") (pin "1") (pinfunction "1_1") (pintype "passive"))
      (node (ref "C4") (pin "2") (pinfunction "2_2") (pintype "passive"))
      (node (ref "C41") (pin "2") (pinfunction "2_2") (pintype "passive"))
      (node (ref "C42") (pin "2") (pinfunction "2_2") (pintype "passive"))
      (node (ref "C43") (pin "1") (pinfunction "1_1") (pintype "passive"))
      (node (ref "C44") (pin "1") (pinfunction "1_1") (pintype "passive"))
      (node (ref "C45") (pin "2") (pinfunction "2_2") (pintype "passive"))
      (node (ref "C46") (pin "1") (pinfunction "1_1") (pintype "passive"))
      (node (ref "C47") (pin "1") (pinfunction "1_1") (pintype "passive"))
      (node (ref "C6") (pin "2") (pinfunction "2_2") (pintype "passive"))
      (node (ref "C7") (pin "2") (pinfunction "2_2") (pintype "passive"))
      (node (ref "C9") (pin "2") (pinfunction "2_2") (pintype "passive"))
      (node (ref "CN1") (pin "13") (pinfunction "G0_13") (pintype "passive"))
      (node (ref "CN1") (pin "14") (pinfunction "G1_14") (pintype "passive"))
      (node (ref "CN1") (pin "21") (pinfunction "B0_21") (pintype "passive"))
      (node (ref "CN1") (pin "22") (pinfunction "B1_22") (pintype "passive"))
      (node (ref "CN1") (pin "29") (pinfunction "GND_29") (pintype "passive"))
      (node (ref "CN1") (pin "3") (pinfunction "GND_3") (pintype "passive"))
      (node (ref "CN1") (pin "36") (pinfunction "GND_36") (pintype "passive"))
      (node (ref "CN1") (pin "41") (pinfunction "GND_41") (pintype "passive"))
      (node (ref "CN1") (pin "42") (pinfunction "GND_42") (pintype "passive"))
      (node (ref "CN1") (pin "5") (pinfunction "R0_5") (pintype "passive"))
      (node (ref "CN1") (pin "6") (pinfunction "R1_6") (pintype "passive"))
      (node (ref "CN2") (pin "10") (pinfunction "10_10") (pintype "passive"))
      (node (ref "CN2") (pin "23") (pinfunction "23_23") (pintype "passive"))
      (node (ref "DS1") (pin "2") (pinfunction "K_2") (pintype "passive"))
      (node (ref "J2") (pin "13") (pinfunction "13_13") (pintype "passive"))
      (node (ref "J2") (pin "14") (pinfunction "14_14") (pintype "passive"))
      (node (ref "J2") (pin "21") (pinfunction "21_21") (pintype "passive"))
      (node (ref "J2") (pin "24") (pinfunction "24_24") (pintype "passive"))
      (node (ref "J2") (pin "3") (pinfunction "3_3") (pintype "passive"))
      (node (ref "J2") (pin "37") (pinfunction "37_37") (pintype "passive"))
      (node (ref "J2") (pin "38") (pinfunction "38_38") (pintype "passive"))
      (node (ref "J2") (pin "4") (pinfunction "4_4") (pintype "passive"))
      (node (ref "J3") (pin "3") (pinfunction "3_3") (pintype "passive"))
      (node (ref "MicroSD1") (pin "10") (pinfunction "PAD1_10") (pintype "power_in"))
      (node (ref "MicroSD1") (pin "11") (pinfunction "PAD2_11") (pintype "power_in"))
      (node (ref "MicroSD1") (pin "12") (pinfunction "PAD3_12") (pintype "power_in"))
      (node (ref "MicroSD1") (pin "13") (pinfunction "PAD4_13") (pintype "power_in"))
      (node (ref "MicroSD1") (pin "6") (pinfunction "VSS_6") (pintype "power_in"))
      (node (ref "R1") (pin "1") (pinfunction "1_1") (pintype "passive"))
      (node (ref "R12") (pin "2") (pinfunction "2_2") (pintype "passive"))
      (node (ref "R15") (pin "1") (pinfunction "1_1") (pintype "passive"))
      (node (ref "R16") (pin "1") (pinfunction "1_1") (pintype "passive"))
      (node (ref "R18") (pin "1") (pinfunction "1_1") (pintype "passive"))
      (node (ref "R19") (pin "1") (pinfunction "1_1") (pintype "passive"))
      (node (ref "R2") (pin "1") (pinfunction "1_1") (pintype "passive"))
      (node (ref "R4") (pin "2") (pinfunction "2_2") (pintype "passive"))
      (node (ref "R5") (pin "2") (pinfunction "2_2") (pintype "passive"))
      (node (ref "R7") (pin "2") (pinfunction "2_2") (pintype "passive"))
      (node (ref "S1") (pin "2") (pinfunction "2_2") (pintype "passive"))
      (node (ref "U1") (pin "0") (pinfunction "GND_0") (pintype "passive"))
      (node (ref "U1") (pin "74") (pinfunction "TV_GND_74") (pintype "passive"))
      (node (ref "U1") (pin "82") (pinfunction "AGND_82") (pintype "passive"))
      (node (ref "U1") (pin "89") (pinfunction "GND_89") (pintype "passive"))
      (node (ref "U2") (pin "1") (pinfunction "GND_1") (pintype "power_in"))
      (node (ref "U3") (pin "1") (pinfunction "GND3_1") (pintype "passive"))
      (node (ref "U3") (pin "12") (pinfunction "GND1_12") (pintype "passive"))
      (node (ref "U3") (pin "13") (pinfunction "GND1_13") (pintype "passive"))
      (node (ref "U3") (pin "15") (pinfunction "AGND_15") (pintype "passive"))
      (node (ref "U3") (pin "17") (pinfunction "AGND_17") (pintype "passive"))
      (node (ref "U3") (pin "21") (pinfunction "EP_21") (pintype "passive"))
      (node (ref "U3") (pin "4") (pinfunction "GND2_4") (pintype "passive"))
      (node (ref "U3") (pin "5") (pinfunction "GND2_5") (pintype "passive"))
      (node (ref "U4") (pin "1") (pinfunction "GND_1") (pintype "power_in"))
      (node (ref "U5") (pin "1") (pinfunction "GND_1") (pintype "power_in"))
      (node (ref "U6") (pin "2") (pinfunction "GND_2") (pintype "passive"))
      (node (ref "U7") (pin "4") (pinfunction "GND_4") (pintype "power_in"))
      (node (ref "U8") (pin "13") (pinfunction "GND_13") (pintype "passive"))
      (node (ref "U8") (pin "2") (pinfunction "GND_2") (pintype "passive"))
      (node (ref "U8") (pin "3") (pinfunction "LED-_3") (pintype "passive"))
      (node (ref "U8") (pin "5") (pinfunction "GND_5") (pintype "passive"))
      (node (ref "USBC1") (pin "0") (pinfunction "0_0") (pintype "passive"))
      (node (ref "USBC1") (pin "A1") (pinfunction "GND_A1") (pintype "passive"))
      (node (ref "USBC1") (pin "A12") (pinfunction "GND_A12") (pintype "passive"))
      (node (ref "USBC1") (pin "B1") (pinfunction "GND_B1") (pintype "passive"))
      (node (ref "USBC1") (pin "B12") (pinfunction "GND_B12") (pintype "passive"))
      (node (ref "X1") (pin "2") (pintype "power_in"))
      (node (ref "X1") (pin "4") (pintype "passive"))
    )
    (net (code "76") (name "AVCC") (class "Default")
      (node (ref "C13") (pin "2") (pinfunction "2_2") (pintype "passive"))
      (node (ref "C24") (pin "2") (pinfunction "2_2") (pintype "passive"))
      (node (ref "U1") (pin "80") (pinfunction "AVCC_80") (pintype "passive"))
      (node (ref "U4") (pin "2") (pinfunction "VOUT_2") (pintype "power_in"))
    )
    (net (code "77") (name "CSI_DVDD") (class "Default")
      (node (ref "C17") (pin "2") (pinfunction "2_2") (pintype "passive"))
      (node (ref "CN2") (pin "15") (pinfunction "15_15") (pintype "passive"))
      (node (ref "JP1") (pin "1") (pintype "power_in"))
      (node (ref "U5") (pin "2") (pinfunction "VOUT_2") (pintype "power_in"))
    )
    (net (code "78") (name "Net-(C33-Pad2)") (class "Default")
      (node (ref "C33") (pin "2") (pinfunction "2_2") (pintype "passive"))
      (node (ref "R12") (pin "1") (pinfunction "1_1") (pintype "passive"))
    )
    (net (code "79") (name "Net-(C34-Pad1)") (class "Default")
      (node (ref "C34") (pin "1") (pinfunction "1_1") (pintype "passive"))
      (node (ref "C37") (pin "2") (pinfunction "2_2") (pintype "passive"))
      (node (ref "C42") (pin "1") (pinfunction "1_1") (pintype "passive"))
      (node (ref "FB1") (pin "2") (pinfunction "2_2") (pintype "passive"))
    )
    (net (code "80") (name "Net-(D1-A)") (class "Default")
      (node (ref "D1") (pin "1") (pinfunction "A_1") (pintype "passive"))
      (node (ref "L4") (pin "2") (pinfunction "2_2") (pintype "passive"))
      (node (ref "U6") (pin "1") (pinfunction "SW_1") (pintype "passive"))
    )
    (net (code "81") (name "Net-(DS1-A)") (class "Default")
      (node (ref "DS1") (pin "1") (pinfunction "A_1") (pintype "passive"))
      (node (ref "R23") (pin "1") (pinfunction "1_1") (pintype "passive"))
    )
    (net (code "82") (name "Net-(DS2-A)") (class "Default")
      (node (ref "DS2") (pin "1") (pinfunction "A_1") (pintype "passive"))
      (node (ref "R24") (pin "1") (pinfunction "1_1") (pintype "passive"))
    )
    (net (code "83") (name "Net-(J1-L)") (class "Default")
      (node (ref "C40") (pin "1") (pinfunction "1_1") (pintype "passive"))
      (node (ref "J1") (pin "6") (pinfunction "L_6") (pintype "passive"))
    )
    (net (code "84") (name "Net-(J1-R)") (class "Default")
      (node (ref "C36") (pin "2") (pinfunction "2_2") (pintype "passive"))
      (node (ref "J1") (pin "4") (pinfunction "R_4") (pintype "passive"))
    )
    (net (code "85") (name "Net-(U1-HOSCI)") (class "Default")
      (node (ref "C35") (pin "2") (pinfunction "2_2") (pintype "passive"))
      (node (ref "U1") (pin "51") (pinfunction "HOSCI_51") (pintype "passive"))
      (node (ref "X1") (pin "1") (pintype "power_in"))
    )
    (net (code "86") (name "Net-(U1-HOSC_OUT)") (class "Default")
      (node (ref "C31") (pin "2") (pinfunction "2_2") (pintype "passive"))
      (node (ref "U1") (pin "52") (pinfunction "HOSC_OUT_52") (pintype "passive"))
      (node (ref "X1") (pin "3") (pinfunction "GND_3") (pintype "power_in"))
    )
    (net (code "87") (name "Net-(U3-FB1)") (class "Default")
      (node (ref "C8") (pin "2") (pinfunction "2_2") (pintype "passive"))
      (node (ref "R4") (pin "1") (pinfunction "1_1") (pintype "passive"))
      (node (ref "R6") (pin "1") (pinfunction "1_1") (pintype "passive"))
      (node (ref "U3") (pin "14") (pinfunction "FB1_14") (pintype "passive"))
    )
    (net (code "88") (name "Net-(U3-FB2)") (class "Default")
      (node (ref "C11") (pin "2") (pinfunction "2_2") (pintype "passive"))
      (node (ref "R7") (pin "1") (pinfunction "1_1") (pintype "passive"))
      (node (ref "R8") (pin "2") (pinfunction "2_2") (pintype "passive"))
      (node (ref "U3") (pin "3") (pinfunction "FB2_3") (pintype "passive"))
    )
    (net (code "89") (name "Net-(U3-FB3)") (class "Default")
      (node (ref "C5") (pin "2") (pinfunction "2_2") (pintype "passive"))
      (node (ref "R3") (pin "1") (pinfunction "1_1") (pintype "passive"))
      (node (ref "R5") (pin "1") (pinfunction "1_1") (pintype "passive"))
      (node (ref "U3") (pin "2") (pinfunction "FB3_2") (pintype "passive"))
    )
    (net (code "90") (name "Net-(U3-LX1)") (class "Default")
      (node (ref "L2") (pin "1") (pinfunction "1_1") (pintype "passive"))
      (node (ref "U3") (pin "11") (pinfunction "LX1_11") (pintype "passive"))
    )
    (net (code "91") (name "Net-(U3-LX2)") (class "Default")
      (node (ref "L3") (pin "2") (pinfunction "2_2") (pintype "passive"))
      (node (ref "U3") (pin "6") (pinfunction "LX2_6") (pintype "passive"))
    )
    (net (code "92") (name "Net-(U3-LX3)") (class "Default")
      (node (ref "L1") (pin "2") (pinfunction "2_2") (pintype "passive"))
      (node (ref "U3") (pin "20") (pinfunction "LX3_20") (pintype "passive"))
    )
    (net (code "93") (name "Net-(U6-EN)") (class "Default")
      (node (ref "R13") (pin "2") (pinfunction "2_2") (pintype "passive"))
      (node (ref "R14") (pin "2") (pinfunction "2_2") (pintype "passive"))
      (node (ref "U6") (pin "4") (pinfunction "EN_4") (pintype "passive"))
    )
    (net (code "94") (name "Net-(U8-LED+)") (class "Default")
      (node (ref "R22") (pin "2") (pinfunction "2_2") (pintype "passive"))
      (node (ref "U8") (pin "4") (pinfunction "LED+_4") (pintype "passive"))
    )
    (net (code "95") (name "Net-(U8-RST_N)") (class "Default")
      (node (ref "C45") (pin "1") (pinfunction "1_1") (pintype "passive"))
      (node (ref "R25") (pin "2") (pinfunction "2_2") (pintype "passive"))
      (node (ref "U8") (pin "6") (pinfunction "RST_N_6") (pintype "passive"))
    )
    (net (code "96") (name "Net-(USBC1-CC1)") (class "Default")
      (node (ref "J3") (pin "2") (pinfunction "2_2") (pintype "passive"))
      (node (ref "USBC1") (pin "A5") (pinfunction "CC1_A5") (pintype "passive"))
      (node (ref "USBC1") (pin "B5") (pinfunction "CC2_B5") (pintype "passive"))
    )
    (net (code "97") (name "VCC_1V1") (class "Default")
      (node (ref "C11") (pin "1") (pinfunction "1_1") (pintype "passive"))
      (node (ref "C14") (pin "2") (pinfunction "2_2") (pintype "passive"))
      (node (ref "C21") (pin "2") (pinfunction "2_2") (pintype "passive"))
      (node (ref "C22") (pin "2") (pinfunction "2_2") (pintype "passive"))
      (node (ref "C23") (pin "2") (pinfunction "2_2") (pintype "passive"))
      (node (ref "L3") (pin "1") (pinfunction "1_1") (pintype "passive"))
      (node (ref "R8") (pin "1") (pinfunction "1_1") (pintype "passive"))
      (node (ref "U1") (pin "22") (pinfunction "VDD_CORE_22") (pintype "passive"))
      (node (ref "U1") (pin "35") (pinfunction "VDD_CORE_35") (pintype "passive"))
      (node (ref "U1") (pin "71") (pinfunction "VDD_CORE_71") (pintype "passive"))
    )
    (net (code "98") (name "VCC_2V5") (class "Default")
      (node (ref "C19") (pin "2") (pinfunction "2_2") (pintype "passive"))
      (node (ref "C20") (pin "2") (pinfunction "2_2") (pintype "passive"))
      (node (ref "C38") (pin "2") (pinfunction "2_2") (pintype "passive"))
      (node (ref "C8") (pin "1") (pinfunction "1_1") (pintype "passive"))
      (node (ref "C9") (pin "1") (pinfunction "1_1") (pintype "passive"))
      (node (ref "L2") (pin "2") (pinfunction "2_2") (pintype "passive"))
      (node (ref "R17") (pin "2") (pinfunction "2_2") (pintype "passive"))
      (node (ref "R6") (pin "2") (pinfunction "2_2") (pintype "passive"))
      (node (ref "U1") (pin "30") (pinfunction "VCC_DRAM_30") (pintype "passive"))
      (node (ref "U1") (pin "31") (pinfunction "VCC_DRAM_31") (pintype "passive"))
      (node (ref "U1") (pin "32") (pinfunction "VCC_DRAM_32") (pintype "passive"))
      (node (ref "U1") (pin "34") (pinfunction "VCC_DRAM_34") (pintype "passive"))
      (node (ref "U1") (pin "36") (pinfunction "VCC_DRAM_36") (pintype "passive"))
    )
    (net (code "99") (name "VCC_2V8") (class "Default")
      (node (ref "C3") (pin "2") (pinfunction "2_2") (pintype "passive"))
      (node (ref "CN2") (pin "21") (pinfunction "21_21") (pintype "passive"))
      (node (ref "JP1") (pin "2") (pintype "power_in"))
      (node (ref "U2") (pin "2") (pinfunction "VOUT_2") (pintype "power_in"))
    )
    (net (code "100") (name "VCC_3V3") (class "Default")
      (node (ref "C12") (pin "2") (pinfunction "2_2") (pintype "passive"))
      (node (ref "C16") (pin "2") (pinfunction "2_2") (pintype "passive"))
      (node (ref "C2") (pin "2") (pinfunction "2_2") (pintype "passive"))
      (node (ref "C25") (pin "1") (pinfunction "1_1") (pintype "passive"))
      (node (ref "C26") (pin "2") (pinfunction "2_2") (pintype "passive"))
      (node (ref "C27") (pin "2") (pinfunction "2_2") (pintype "passive"))
      (node (ref "C28") (pin "2") (pinfunction "2_2") (pintype "passive"))
      (node (ref "C4") (pin "1") (pinfunction "1_1") (pintype "passive"))
      (node (ref "C43") (pin "2") (pinfunction "2_2") (pintype "passive"))
      (node (ref "C44") (pin "2") (pinfunction "2_2") (pintype "passive"))
      (node (ref "C5") (pin "1") (pinfunction "1_1") (pintype "passive"))
      (node (ref "CN1") (pin "31") (pinfunction "DISP_31") (pintype "passive"))
      (node (ref "CN1") (pin "4") (pinfunction "VCC_4") (pintype "passive"))
      (node (ref "CN2") (pin "14") (pinfunction "14_14") (pintype "passive"))
      (node (ref "J2") (pin "2") (pinfunction "2_2") (pintype "passive"))
      (node (ref "J2") (pin "39") (pinfunction "39_39") (pintype "passive"))
      (node (ref "L1") (pin "1") (pinfunction "1_1") (pintype "passive"))
      (node (ref "MicroSD1") (pin "4") (pinfunction "VDD_4") (pintype "power_in"))
      (node (ref "R10") (pin "2") (pinfunction "2_2") (pintype "passive"))
      (node (ref "R20") (pin "2") (pinfunction "2_2") (pintype "passive"))
      (node (ref "R21") (pin "2") (pinfunction "2_2") (pintype "passive"))
      (node (ref "R22") (pin "1") (pinfunction "1_1") (pintype "passive"))
      (node (ref "R24") (pin "2") (pinfunction "2_2") (pintype "passive"))
      (node (ref "R25") (pin "1") (pinfunction "1_1") (pintype "passive"))
      (node (ref "R3") (pin "2") (pinfunction "2_2") (pintype "passive"))
      (node (ref "R9") (pin "2") (pinfunction "2_2") (pintype "passive"))
      (node (ref "U1") (pin "20") (pinfunction "VCC_IO_20") (pintype "passive"))
      (node (ref "U1") (pin "4") (pinfunction "HPVCC_4") (pintype "passive"))
      (node (ref "U1") (pin "5") (pinfunction "VCC_IO_5") (pintype "passive"))
      (node (ref "U1") (pin "50") (pinfunction "VCC_IO_50") (pintype "passive"))
      (node (ref "U1") (pin "67") (pinfunction "VCC_USB_67") (pintype "passive"))
      (node (ref "U2") (pin "3") (pinfunction "VIN_3") (pintype "power_in"))
      (node (ref "U4") (pin "3") (pinfunction "VIN_3") (pintype "power_in"))
      (node (ref "U5") (pin "3") (pinfunction "VIN_3") (pintype "power_in"))
      (node (ref "U7") (pin "3") (pinfunction "WP_3") (pintype "power_in"))
      (node (ref "U7") (pin "7") (pinfunction "Hold_7") (pintype "power_in"))
      (node (ref "U7") (pin "8") (pinfunction "VCC_8") (pintype "power_in"))
      (node (ref "U8") (pin "10") (pinfunction "VCC_10") (pintype "passive"))
      (node (ref "U8") (pin "11") (pinfunction "IOVCC_11") (pintype "passive"))
    )
    (net (code "101") (name "VCC_TV") (class "Default")
      (node (ref "C29") (pin "2") (pinfunction "2_2") (pintype "passive"))
      (node (ref "R10") (pin "1") (pinfunction "1_1") (pintype "passive"))
      (node (ref "U1") (pin "73") (pinfunction "TV_VCC_73") (pintype "passive"))
    )
    (net (code "102") (name "unconnected-(CN1-NC-Pad35)") (class "Default")
      (node (ref "CN1") (pin "35") (pinfunction "NC_35") (pintype "passive+no_connect"))
    )
    (net (code "103") (name "unconnected-(CN2-Pad1)") (class "Default")
      (node (ref "CN2") (pin "1") (pinfunction "1_1") (pintype "passive+no_connect"))
    )
    (net (code "104") (name "unconnected-(CN2-Pad2)") (class "Default")
      (node (ref "CN2") (pin "2") (pinfunction "2_2") (pintype "passive+no_connect"))
    )
    (net (code "105") (name "unconnected-(CN2-Pad24)") (class "Default")
      (node (ref "CN2") (pin "24") (pinfunction "24_24") (pintype "passive+no_connect"))
    )
    (net (code "106") (name "unconnected-(J1-L_DET-Pad7)") (class "Default")
      (node (ref "J1") (pin "7") (pinfunction "L_DET_7") (pintype "passive"))
    )
    (net (code "107") (name "unconnected-(J1-R_DET-Pad5)") (class "Default")
      (node (ref "J1") (pin "5") (pinfunction "R_DET_5") (pintype "passive"))
    )
    (net (code "108") (name "unconnected-(U8-NC-Pad1)") (class "Default")
      (node (ref "U8") (pin "1") (pinfunction "NC_1") (pintype "passive"))
    )
    (net (code "109") (name "unconnected-(U8-NC-Pad14)") (class "Default")
      (node (ref "U8") (pin "14") (pinfunction "NC_14") (pintype "passive"))
    )
    (net (code "110") (name "unconnected-(USBC1-SBU1-PadA8)") (class "Default")
      (node (ref "USBC1") (pin "A8") (pinfunction "SBU1_A8") (pintype "passive"))
    )
    (net (code "111") (name "unconnected-(USBC1-SBU2-PadB8)") (class "Default")
      (node (ref "USBC1") (pin "B8") (pinfunction "SBU2_B8") (pintype "passive"))
    )
  )
)
